# SparkFun_Qwiic_CO2_Sensor_SCD41.net
KiCad netlist of a schematic drawn in EAGLE
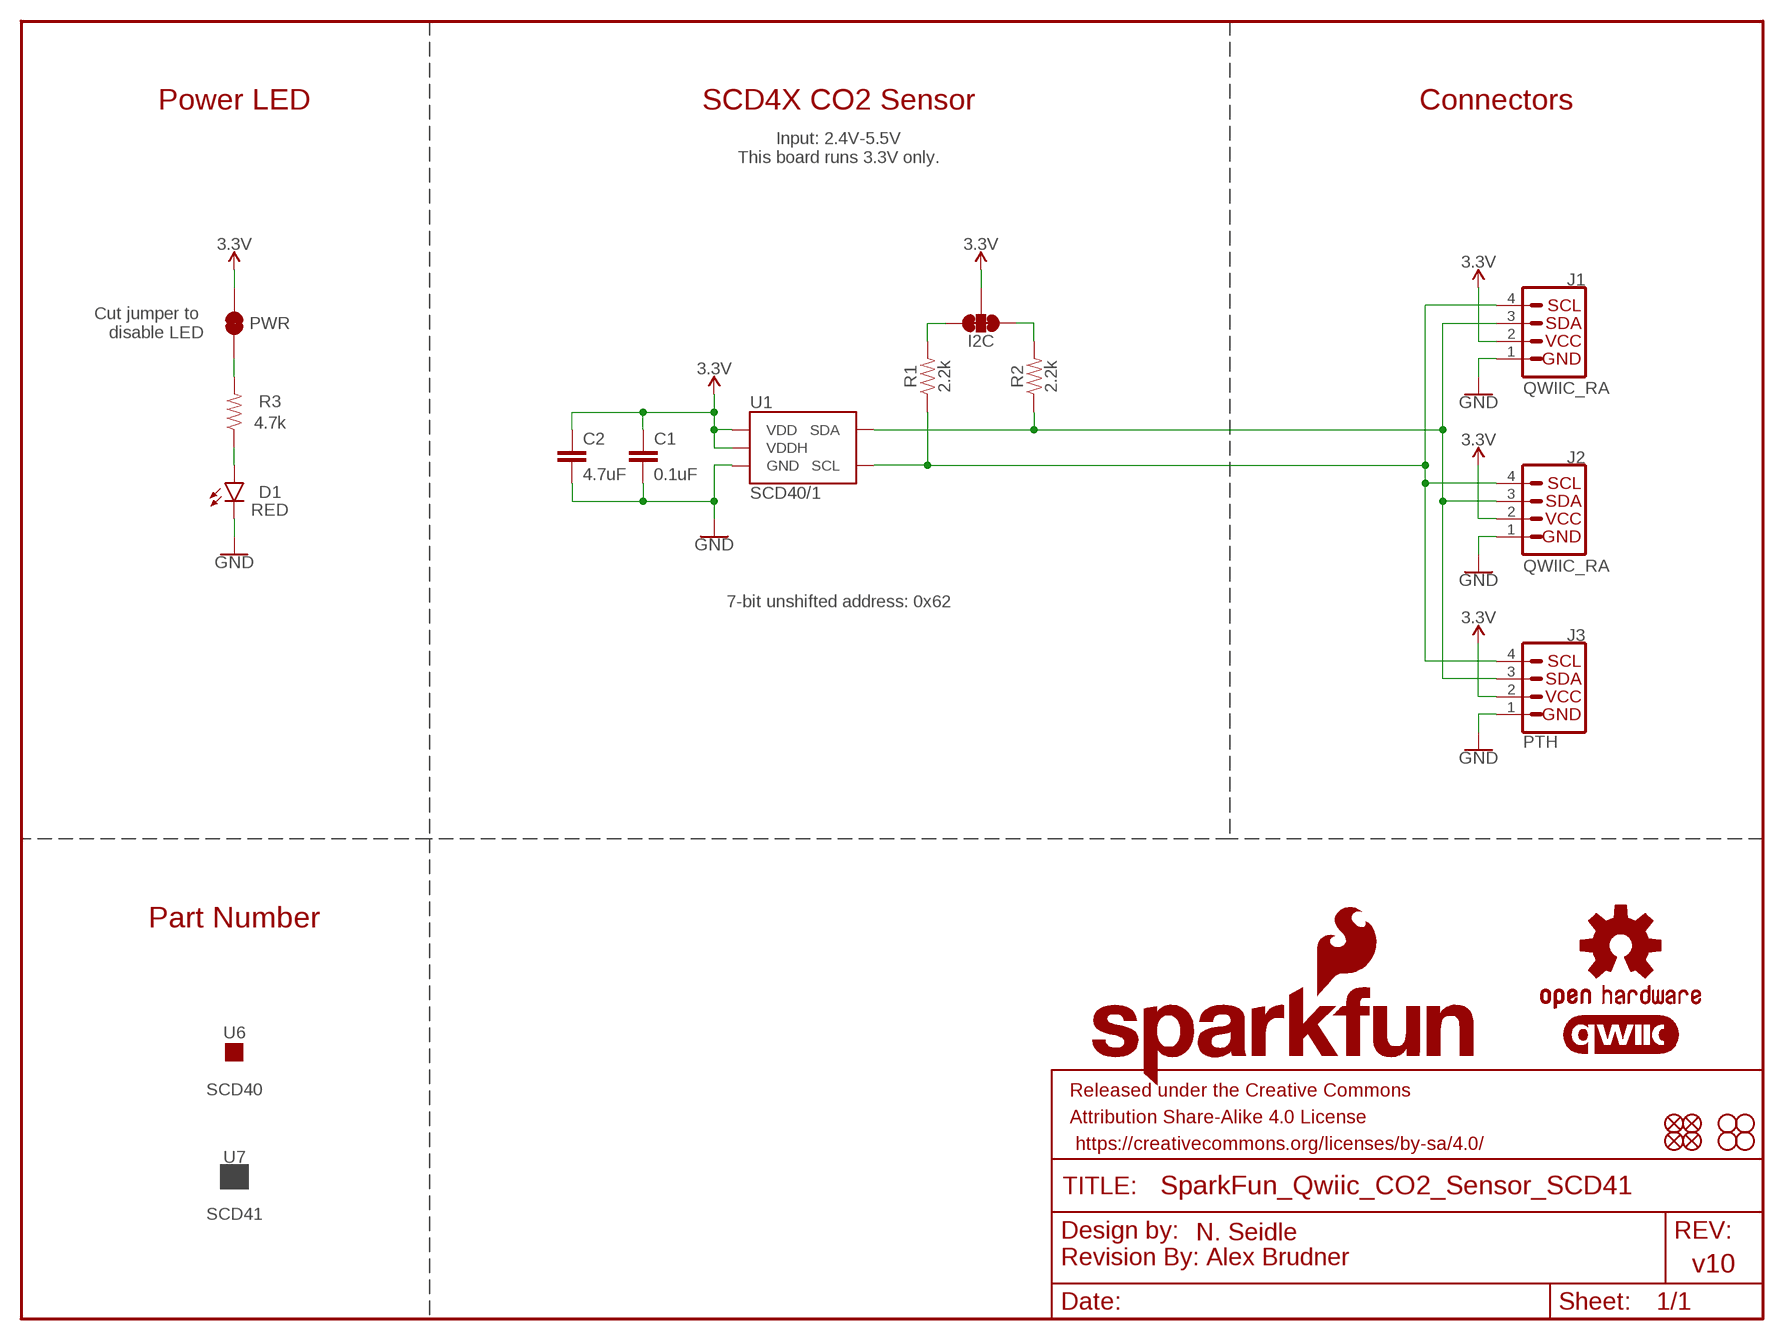
[diagram p0: schematic, sheet 1]

(export (version "E")
  (design (tool "Eeschema 10.0.6"))
  (components
    (comp (ref "C1")
      (value "0.1uF")
      (footprint "eagle-import:0603")
      (libsource (lib "eagle-import") (part "0.1UF-0603-25V-10%-X7R-WE"))
    )
    (comp (ref "C2")
      (value "4.7uF")
      (footprint "eagle-import:0603")
      (libsource (lib "eagle-import") (part "4.7UF-0603-6.3V-(10%)"))
    )
    (comp (ref "D1")
      (value "RED")
      (footprint "eagle-import:LED-0603")
      (libsource (lib "eagle-import") (part "LED-RED_0603-KB"))
    )
    (comp (ref "FD1")
      (value "FIDUCIALUFIDUCIAL")
      (footprint "eagle-import:FIDUCIAL-MICRO")
      (libsource (lib "eagle-import") (part "FIDUCIALUFIDUCIAL"))
    )
    (comp (ref "FD2")
      (value "FIDUCIALUFIDUCIAL")
      (footprint "eagle-import:FIDUCIAL-MICRO")
      (libsource (lib "eagle-import") (part "FIDUCIALUFIDUCIAL"))
    )
    (comp (ref "FD3")
      (value "FIDUCIALUFIDUCIAL")
      (footprint "eagle-import:FIDUCIAL-MICRO")
      (libsource (lib "eagle-import") (part "FIDUCIALUFIDUCIAL"))
    )
    (comp (ref "FD4")
      (value "FIDUCIALUFIDUCIAL")
      (footprint "eagle-import:FIDUCIAL-MICRO")
      (libsource (lib "eagle-import") (part "FIDUCIALUFIDUCIAL"))
    )
    (comp (ref "FRAME1")
      (value "FRAME-LETTER")
      (footprint "eagle-import:CREATIVE_COMMONS")
      (fields
        (field (name "BASEDON") "Revision By: Alex Brudner")
        (field (name "DESIGNER") "N. Seidle")
        (field (name "REV") "v10")
      )
      (libsource (lib "eagle-import") (part "FRAME-LETTER"))
    )
    (comp (ref "H1")
      (value "STAND-OFF")
      (footprint "eagle-import:STAND-OFF")
      (libsource (lib "eagle-import") (part "STAND-OFF"))
    )
    (comp (ref "H2")
      (value "STAND-OFF")
      (footprint "eagle-import:STAND-OFF")
      (libsource (lib "eagle-import") (part "STAND-OFF"))
    )
    (comp (ref "H3")
      (value "STAND-OFF")
      (footprint "eagle-import:STAND-OFF")
      (libsource (lib "eagle-import") (part "STAND-OFF"))
    )
    (comp (ref "H4")
      (value "STAND-OFF")
      (footprint "eagle-import:STAND-OFF")
      (libsource (lib "eagle-import") (part "STAND-OFF"))
    )
    (comp (ref "I2C")
      (value "I2C")
      (footprint "eagle-import:SMT-JUMPER_3_2-NC_TRACE_SILK")
      (libsource (lib "eagle-import") (part "JUMPER-SMT_3_2-NC_TRACE_SILK"))
    )
    (comp (ref "J1")
      (value "QWIIC_RA")
      (footprint "eagle-import:JST04_1MM_RA")
      (libsource (lib "eagle-import") (part "QWIIC_CONNECTORJS-1MM"))
    )
    (comp (ref "J2")
      (value "QWIIC_RA")
      (footprint "eagle-import:JST04_1MM_RA")
      (libsource (lib "eagle-import") (part "QWIIC_CONNECTORJS-1MM"))
    )
    (comp (ref "J3")
      (value "PTH")
      (footprint "eagle-import:1X04_NO_SILK")
      (libsource (lib "eagle-import") (part "I2C_STANDARD_NO_SILK"))
    )
    (comp (ref "LOGO1")
      (value "QWIIC_LOGO_CONNECTOR")
      (footprint "eagle-import:QWIIC_5.5MM")
      (libsource (lib "eagle-import") (part "QWIIC_LOGO_CONNECTOR"))
    )
    (comp (ref "LOGO2")
      (value "OSHW-LOGOS")
      (footprint "eagle-import:OSHW-LOGO-S")
      (libsource (lib "eagle-import") (part "OSHW-LOGOS"))
    )
    (comp (ref "LOGO3")
      (value "SFE_LOGO_NAME_FLAMEBLANK")
      (footprint "eagle-import:BLANK")
      (libsource (lib "eagle-import") (part "SFE_LOGO_NAME_FLAMEBLANK"))
    )
    (comp (ref "PWR")
      (value "PWR")
      (footprint "eagle-import:SMT-JUMPER_2_NC_TRACE_SILK")
      (libsource (lib "eagle-import") (part "JUMPER-SMT_2_NC_TRACE_SILK"))
    )
    (comp (ref "R1")
      (value "2.2k")
      (footprint "eagle-import:0603")
      (libsource (lib "eagle-import") (part "2.2KOHM-0603-1/10W-1%"))
    )
    (comp (ref "R2")
      (value "2.2k")
      (footprint "eagle-import:0603")
      (libsource (lib "eagle-import") (part "2.2KOHM-0603-1/10W-1%"))
    )
    (comp (ref "R3")
      (value "4.7k")
      (footprint "eagle-import:0603")
      (libsource (lib "eagle-import") (part "4.7KOHM-0603-1/10W-1%"))
    )
    (comp (ref "U1")
      (value "SCD40/1")
      (footprint "eagle-import:SCD4X")
      (libsource (lib "eagle-import") (part "SCD4X"))
    )
    (comp (ref "U6")
      (value "SCD40")
      (footprint "eagle-import:PRODUCT_IDENT_NO_NO-SILK")
      (libsource (lib "eagle-import") (part "PROD_ID_NO-PASTE_NO_SILK"))
    )
    (comp (ref "U7")
      (value "SCD41")
      (footprint "eagle-import:PRODUCT_IDENT_PASTE_NO-SILK")
      (libsource (lib "eagle-import") (part "PROD_ID_PASTE_NO-SILK"))
    )
  )
  (nets
    (net (code "1") (name "3.3V") (class "Default")
      (node (ref "C1") (pin "1") (pinfunction "1_1") (pintype "passive"))
      (node (ref "C2") (pin "1") (pinfunction "1_1") (pintype "passive"))
      (node (ref "I2C") (pin "2") (pinfunction "2_2") (pintype "passive"))
      (node (ref "J1") (pin "2") (pinfunction "2_2") (pintype "power_in"))
      (node (ref "J2") (pin "2") (pinfunction "2_2") (pintype "power_in"))
      (node (ref "J3") (pin "2") (pinfunction "2_2") (pintype "power_in"))
      (node (ref "PWR") (pin "2") (pinfunction "2_2") (pintype "passive"))
      (node (ref "U1") (pin "19") (pinfunction "VDDH_19") (pintype "power_in"))
      (node (ref "U1") (pin "7") (pinfunction "VDD_7") (pintype "power_in"))
    )
    (net (code "2") (name "GND") (class "Default")
      (node (ref "C1") (pin "2") (pinfunction "2_2") (pintype "passive"))
      (node (ref "C2") (pin "2") (pinfunction "2_2") (pintype "passive"))
      (node (ref "D1") (pin "C") (pinfunction "C_C") (pintype "passive"))
      (node (ref "J1") (pin "1") (pinfunction "1_1") (pintype "power_in"))
      (node (ref "J2") (pin "1") (pinfunction "1_1") (pintype "power_in"))
      (node (ref "J3") (pin "1") (pinfunction "1_1") (pintype "power_in"))
      (node (ref "U1") (pin "20") (pinfunction "GND_20") (pintype "power_in"))
      (node (ref "U1") (pin "6") (pinfunction "GND_6") (pintype "power_in"))
      (node (ref "U1") (pin "CP") (pinfunction "GND_CP") (pintype "power_in"))
    )
    (net (code "3") (name "Net-(D1-PadA)") (class "Default")
      (node (ref "D1") (pin "A") (pinfunction "A_A") (pintype "passive"))
      (node (ref "R3") (pin "1") (pinfunction "1_1") (pintype "passive"))
    )
    (net (code "4") (name "Net-(I2C-Pad1)") (class "Default")
      (node (ref "I2C") (pin "1") (pinfunction "1_1") (pintype "passive"))
      (node (ref "R2") (pin "2") (pinfunction "2_2") (pintype "passive"))
    )
    (net (code "5") (name "Net-(I2C-Pad3)") (class "Default")
      (node (ref "I2C") (pin "3") (pinfunction "3_3") (pintype "passive"))
      (node (ref "R1") (pin "2") (pinfunction "2_2") (pintype "passive"))
    )
    (net (code "6") (name "Net-(PWR-Pad1)") (class "Default")
      (node (ref "PWR") (pin "1") (pinfunction "1_1") (pintype "passive"))
      (node (ref "R3") (pin "2") (pinfunction "2_2") (pintype "passive"))
    )
    (net (code "7") (name "Net-(U1-SCL)") (class "Default")
      (node (ref "J1") (pin "4") (pinfunction "4_4") (pintype "passive"))
      (node (ref "J2") (pin "4") (pinfunction "4_4") (pintype "passive"))
      (node (ref "J3") (pin "4") (pinfunction "4_4") (pintype "passive"))
      (node (ref "R1") (pin "1") (pinfunction "1_1") (pintype "passive"))
      (node (ref "U1") (pin "9") (pinfunction "SCL_9") (pintype "bidirectional"))
    )
    (net (code "8") (name "Net-(U1-SDA)") (class "Default")
      (node (ref "J1") (pin "3") (pinfunction "3_3") (pintype "passive"))
      (node (ref "J2") (pin "3") (pinfunction "3_3") (pintype "passive"))
      (node (ref "J3") (pin "3") (pinfunction "3_3") (pintype "passive"))
      (node (ref "R2") (pin "1") (pinfunction "1_1") (pintype "passive"))
      (node (ref "U1") (pin "10") (pinfunction "SDA_10") (pintype "bidirectional"))
    )
  )
)
